# design.net
KiCad netlist of a schematic drawn in Altium Designer
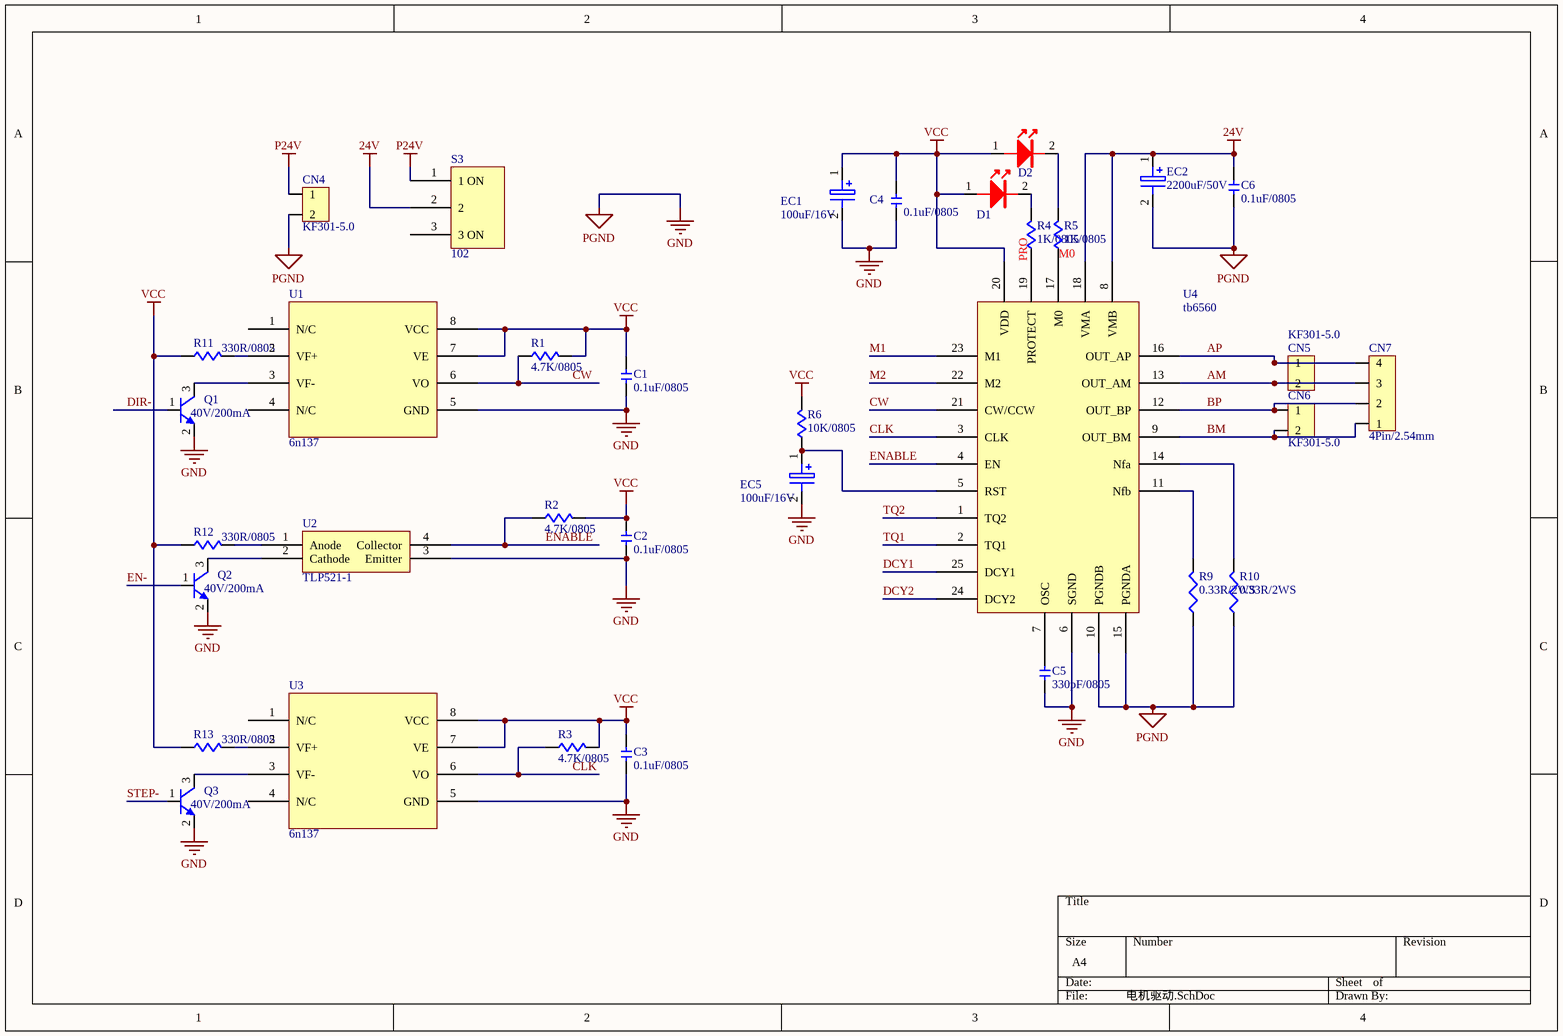
[diagram p0: 电机驱动.SchDoc]

(export (version "E")
  (design (tool "Eeschema 10.0.6"))
  (components
    (comp (ref "C1")
      (value "0.1uF/0805")
      (footprint "WSC0805")
      (description "R21050165/工业C/消费C/贴片电容/0.1uF/±10%/50V/X7R/0805")
      (libsource (lib "Capacitor_21") (part "R21050165"))
    )
    (comp (ref "C2")
      (value "0.1uF/0805")
      (footprint "WSC0805")
      (description "R21050165/工业C/消费C/贴片电容/0.1uF/±10%/50V/X7R/0805")
      (libsource (lib "Capacitor_21") (part "R21050165"))
    )
    (comp (ref "C3")
      (value "0.1uF/0805")
      (footprint "WSC0805")
      (description "R21050165/工业C/消费C/贴片电容/0.1uF/±10%/50V/X7R/0805")
      (libsource (lib "Capacitor_21") (part "R21050165"))
    )
    (comp (ref "C4")
      (value "0.1uF/0805")
      (footprint "WSC0805")
      (description "R21050165/工业C/消费C/贴片电容/0.1uF/±10%/50V/X7R/0805")
      (libsource (lib "Capacitor_21") (part "R21050165"))
    )
    (comp (ref "C5")
      (value "330pF/0805")
      (footprint "WSC0805")
      (description "R21180028/消费C/台系贴片电容/330pF/±10%/50V/X7R/0805")
      (libsource (lib "Capacitor_21") (part "R21180028"))
    )
    (comp (ref "C6")
      (value "0.1uF/0805")
      (footprint "WSC0805")
      (description "R21050005/工业B/消费B/贴片电容/0.1uF±10%/50V/X7R/0805")
      (libsource (lib "Capacitor_21") (part "R21050005"))
    )
    (comp (ref "CN4")
      (value "KF301-5.0")
      (footprint "KF301-5.0")
      (libsource (lib "Integrated_Library1") (part "KF301-5.0"))
    )
    (comp (ref "CN5")
      (value "KF301-5.0")
      (footprint "KF301-5.0")
      (libsource (lib "Integrated_Library1") (part "KF301-5.0"))
    )
    (comp (ref "CN6")
      (value "KF301-5.0")
      (footprint "KF301-5.0")
      (libsource (lib "Integrated_Library1") (part "KF301-5.0"))
    )
    (comp (ref "CN7")
      (value "4Pin/2.54mm")
      (footprint "THT-CON4-2.54-2.54A/S-H8.5")
      (description "R30041122/消费B/普通插座/单排排母/4PIN/3A/单排/直脚/鱼叉母座/2.54mm/-40~105℃/H=8.5mm")
      (libsource (lib "Connector_30") (part "R30041122"))
    )
    (comp (ref "D1")
      (value "LED0805")
      (footprint "SD0805")
      (description "R26010108/工业A/消费A/发光二极管/红色/61mcd@20mA/0805SMD/LED0805")
      (libsource (lib "Semiconductor_26") (part "R26010108"))
    )
    (comp (ref "D2")
      (value "LED0805")
      (footprint "SD0805")
      (description "R26010108/工业A/消费A/发光二极管/红色/61mcd@20mA/0805SMD/LED0805")
      (libsource (lib "Semiconductor_26") (part "R26010108"))
    )
    (comp (ref "EC1")
      (value "100uF/16V")
      (footprint "CAPC2-5-5*11A/D")
      (description "R21010764/消费C/铝电解电容/105℃/100uF/16V/φ5*11")
      (libsource (lib "Capacitor_21") (part "R21010764"))
    )
    (comp (ref "EC2")
      (value "2200uF/50V")
      (footprint "CAPC2-7.5-18*35.5A/S")
      (description "R21110099/工业B/铝电解电容/105℃/2200uF/50V/低阻/φ18*35.5/7000h")
      (libsource (lib "Capacitor_21") (part "R21110099"))
    )
    (comp (ref "EC5")
      (value "100uF/16V")
      (footprint "CAPC2-5-5*11A/D")
      (description "R21010764/消费C/铝电解电容/105℃/100uF/16V/φ5*11")
      (libsource (lib "Capacitor_21") (part "R21010764"))
    )
    (comp (ref "Q1")
      (value "40V/200mA")
      (footprint "WSOT-23")
      (description "R26080001/工业A/消费A/小信号三极管/NPN/40V/200mA/SOT-23")
      (libsource (lib "Semiconductor_26") (part "R26080001"))
    )
    (comp (ref "Q2")
      (value "40V/200mA")
      (footprint "WSOT-23")
      (description "R26080001/工业A/消费A/小信号三极管/NPN/40V/200mA/SOT-23")
      (libsource (lib "Semiconductor_26") (part "R26080001"))
    )
    (comp (ref "Q3")
      (value "40V/200mA")
      (footprint "WSOT-23")
      (description "R26080001/工业A/消费A/小信号三极管/NPN/40V/200mA/SOT-23")
      (libsource (lib "Semiconductor_26") (part "R26080001"))
    )
    (comp (ref "R1")
      (value "4.7K/0805")
      (footprint "WSR0805")
      (description "R20180039/工业A/消费A/贴片电阻/1/8W/4.7KΩ±5%/0805")
      (libsource (lib "Resistor_20") (part "R20180039"))
    )
    (comp (ref "R2")
      (value "4.7K/0805")
      (footprint "WSR0805")
      (description "R20180039/工业A/消费A/贴片电阻/1/8W/4.7KΩ±5%/0805")
      (libsource (lib "Resistor_20") (part "R20180039"))
    )
    (comp (ref "R3")
      (value "4.7K/0805")
      (footprint "WSR0805")
      (description "R20180039/工业A/消费A/贴片电阻/1/8W/4.7KΩ±5%/0805")
      (libsource (lib "Resistor_20") (part "R20180039"))
    )
    (comp (ref "R4")
      (value "1K/0805")
      (footprint "WSR0805")
      (description "R20180023/工业A/消费A/贴片电阻/1/8W/1KΩ±5%/0805")
      (libsource (lib "Resistor_20") (part "R20180023"))
    )
    (comp (ref "R5")
      (value "1K/0805")
      (footprint "WSR0805")
      (description "R20180023/工业A/消费A/贴片电阻/1/8W/1KΩ±5%/0805")
      (libsource (lib "Resistor_20") (part "R20180023"))
    )
    (comp (ref "R6")
      (value "10K/0805")
      (footprint "WSR0805")
      (description "R20180048/工业A/消费A/贴片电阻/1/8W/10KΩ±5%/0805")
      (libsource (lib "Resistor_20") (part "R20180048"))
    )
    (comp (ref "R9")
      (value "0.33R/2WS")
      (footprint "R2-7.5-4.5A/S")
      (description "R20040079/工业B/消费B/无感线绕电阻/2WS/0.33Ω±5%/小型4.5*11")
      (libsource (lib "Resistor_20") (part "R20040079"))
    )
    (comp (ref "R10")
      (value "0.33R/2WS")
      (footprint "R2-7.5-4.5A/S")
      (description "R20040079/工业B/消费B/无感线绕电阻/2WS/0.33Ω±5%/小型4.5*11")
      (libsource (lib "Resistor_20") (part "R20040079"))
    )
    (comp (ref "R11")
      (value "330R/0805")
      (footprint "WSR0805")
      (description "R20180090/工业A/消费A/贴片电阻/1/8W/330Ω±5%/0805")
      (libsource (lib "Resistor_20") (part "R20180090"))
    )
    (comp (ref "R12")
      (value "330R/0805")
      (footprint "WSR0805")
      (description "R20180090/工业A/消费A/贴片电阻/1/8W/330Ω±5%/0805")
      (libsource (lib "Resistor_20") (part "R20180090"))
    )
    (comp (ref "R13")
      (value "330R/0805")
      (footprint "WSR0805")
      (description "R20180090/工业A/消费A/贴片电阻/1/8W/330Ω±5%/0805")
      (libsource (lib "Resistor_20") (part "R20180090"))
    )
    (comp (ref "S3")
      (value "102")
      (footprint "开关")
      (libsource (lib "Integrated_Library1") (part "switch mts102"))
    )
    (comp (ref "U1")
      (value "6n137")
      (footprint "6N137")
      (description "6n137高速度光耦")
      (libsource (lib "Integrated_Library1") (part "6n137"))
    )
    (comp (ref "U2")
      (value "TLP521-1")
      (footprint "tlp521 - duplicate")
      (description "TLP521-1/光耦")
      (libsource (lib "Integrated_Library1") (part "TLP521"))
    )
    (comp (ref "U3")
      (value "6n137")
      (footprint "6N137")
      (description "6n137高速度光耦")
      (libsource (lib "Integrated_Library1") (part "6n137"))
    )
    (comp (ref "U4")
      (value "tb6560")
      (footprint "TB6560")
      (description "tb6560、步进电机驱动")
      (libsource (lib "Integrated_Library1") (part "tb6560"))
    )
  )
  (nets
    (net (code "1") (name "/AM") (class "Default")
      (node (ref "CN5") (pin "2") (pinfunction "2_2") (pintype "passive"))
      (node (ref "CN7") (pin "3") (pinfunction "3_3") (pintype "passive"))
      (node (ref "U4") (pin "13") (pinfunction "OUT_AM_13") (pintype "passive"))
    )
    (net (code "2") (name "/AP") (class "Default")
      (node (ref "CN5") (pin "1") (pinfunction "1_1") (pintype "passive"))
      (node (ref "CN7") (pin "4") (pinfunction "4_4") (pintype "passive"))
      (node (ref "U4") (pin "16") (pinfunction "OUT_AP_16") (pintype "passive"))
    )
    (net (code "3") (name "/BM") (class "Default")
      (node (ref "CN6") (pin "2") (pinfunction "2_2") (pintype "passive"))
      (node (ref "CN7") (pin "1") (pinfunction "1_1") (pintype "passive"))
      (node (ref "U4") (pin "9") (pinfunction "OUT_BM_9") (pintype "passive"))
    )
    (net (code "4") (name "/BP") (class "Default")
      (node (ref "CN6") (pin "1") (pinfunction "1_1") (pintype "passive"))
      (node (ref "CN7") (pin "2") (pinfunction "2_2") (pintype "passive"))
      (node (ref "U4") (pin "12") (pinfunction "OUT_BP_12") (pintype "passive"))
    )
    (net (code "5") (name "/CLK") (class "Default")
      (node (ref "R3") (pin "1") (pinfunction "1_1") (pintype "passive"))
      (node (ref "U3") (pin "6") (pinfunction "VO_6") (pintype "passive"))
      (node (ref "U4") (pin "3") (pinfunction "CLK_3") (pintype "passive"))
    )
    (net (code "6") (name "/CW") (class "Default")
      (node (ref "R1") (pin "1") (pinfunction "1_1") (pintype "passive"))
      (node (ref "U1") (pin "6") (pinfunction "VO_6") (pintype "passive"))
      (node (ref "U4") (pin "21") (pinfunction "CW/CCW_21") (pintype "passive"))
    )
    (net (code "7") (name "/DCY1") (class "Default")
      (node (ref "U4") (pin "25") (pinfunction "DCY1_25") (pintype "passive"))
    )
    (net (code "8") (name "/DCY2") (class "Default")
      (node (ref "U4") (pin "24") (pinfunction "DCY2_24") (pintype "passive"))
    )
    (net (code "9") (name "/DIR-") (class "Default")
      (node (ref "Q1") (pin "1") (pinfunction "B_1") (pintype "passive"))
    )
    (net (code "10") (name "/EN-") (class "Default")
      (node (ref "Q2") (pin "1") (pinfunction "B_1") (pintype "passive"))
    )
    (net (code "11") (name "/ENABLE") (class "Default")
      (node (ref "R2") (pin "1") (pinfunction "1_1") (pintype "passive"))
      (node (ref "U2") (pin "4") (pinfunction "Collector_4") (pintype "passive"))
      (node (ref "U4") (pin "4") (pinfunction "EN_4") (pintype "passive"))
    )
    (net (code "12") (name "/M0") (class "Default")
      (node (ref "R5") (pin "1") (pinfunction "1_1") (pintype "passive"))
      (node (ref "U4") (pin "17") (pinfunction "M0_17") (pintype "passive"))
    )
    (net (code "13") (name "/M1") (class "Default")
      (node (ref "U4") (pin "23") (pinfunction "M1_23") (pintype "passive"))
    )
    (net (code "14") (name "/M2") (class "Default")
      (node (ref "U4") (pin "22") (pinfunction "M2_22") (pintype "passive"))
    )
    (net (code "15") (name "/PRO") (class "Default")
      (node (ref "R4") (pin "1") (pinfunction "1_1") (pintype "passive"))
      (node (ref "U4") (pin "19") (pinfunction "PROTECT_19") (pintype "passive"))
    )
    (net (code "16") (name "/STEP-") (class "Default")
      (node (ref "Q3") (pin "1") (pinfunction "B_1") (pintype "passive"))
    )
    (net (code "17") (name "/TQ1") (class "Default")
      (node (ref "U4") (pin "2") (pinfunction "TQ1_2") (pintype "passive"))
    )
    (net (code "18") (name "/TQ2") (class "Default")
      (node (ref "U4") (pin "1") (pinfunction "TQ2_1") (pintype "passive"))
    )
    (net (code "19") (name "24V") (class "Default")
      (node (ref "C6") (pin "2") (pinfunction "2_2") (pintype "passive"))
      (node (ref "EC2") (pin "1") (pinfunction "1_1") (pintype "passive"))
      (node (ref "S3") (pin "2") (pinfunction "2_2") (pintype "passive"))
      (node (ref "U4") (pin "18") (pinfunction "VMA_18") (pintype "passive"))
      (node (ref "U4") (pin "8") (pinfunction "VMB_8") (pintype "passive"))
    )
    (net (code "20") (name "GND") (class "Default")
      (node (ref "C1") (pin "1") (pinfunction "1_1") (pintype "passive"))
      (node (ref "C2") (pin "1") (pinfunction "1_1") (pintype "passive"))
      (node (ref "C3") (pin "1") (pinfunction "1_1") (pintype "passive"))
      (node (ref "C4") (pin "1") (pinfunction "1_1") (pintype "passive"))
      (node (ref "C5") (pin "1") (pinfunction "1_1") (pintype "passive"))
      (node (ref "C6") (pin "1") (pinfunction "1_1") (pintype "passive"))
      (node (ref "CN4") (pin "2") (pinfunction "2_2") (pintype "passive"))
      (node (ref "EC1") (pin "2") (pinfunction "2_2") (pintype "passive"))
      (node (ref "EC2") (pin "2") (pinfunction "2_2") (pintype "passive"))
      (node (ref "EC5") (pin "2") (pinfunction "2_2") (pintype "passive"))
      (node (ref "Q1") (pin "2") (pinfunction "E_2") (pintype "passive"))
      (node (ref "Q2") (pin "2") (pinfunction "E_2") (pintype "passive"))
      (node (ref "Q3") (pin "2") (pinfunction "E_2") (pintype "passive"))
      (node (ref "R10") (pin "1") (pinfunction "1_1") (pintype "passive"))
      (node (ref "R9") (pin "1") (pinfunction "1_1") (pintype "passive"))
      (node (ref "U1") (pin "5") (pinfunction "GND_5") (pintype "passive"))
      (node (ref "U2") (pin "3") (pinfunction "Emitter_3") (pintype "passive"))
      (node (ref "U3") (pin "5") (pinfunction "GND_5") (pintype "passive"))
      (node (ref "U4") (pin "10") (pinfunction "PGNDB_10") (pintype "passive"))
      (node (ref "U4") (pin "15") (pinfunction "PGNDA_15") (pintype "passive"))
      (node (ref "U4") (pin "6") (pinfunction "SGND_6") (pintype "passive"))
    )
    (net (code "21") (name "Net-(D1-K)") (class "Default")
      (node (ref "D1") (pin "2") (pinfunction "K_2") (pintype "passive"))
      (node (ref "R4") (pin "2") (pinfunction "2_2") (pintype "passive"))
    )
    (net (code "22") (name "Net-(D2-K)") (class "Default")
      (node (ref "D2") (pin "2") (pinfunction "K_2") (pintype "passive"))
      (node (ref "R5") (pin "2") (pinfunction "2_2") (pintype "passive"))
    )
    (net (code "23") (name "Net-(Q1-C)") (class "Default")
      (node (ref "Q1") (pin "3") (pinfunction "C_3") (pintype "passive"))
      (node (ref "U1") (pin "3") (pinfunction "VF-_3") (pintype "passive"))
    )
    (net (code "24") (name "Net-(Q2-C)") (class "Default")
      (node (ref "Q2") (pin "3") (pinfunction "C_3") (pintype "passive"))
      (node (ref "U2") (pin "2") (pinfunction "Cathode_2") (pintype "passive"))
    )
    (net (code "25") (name "Net-(Q3-C)") (class "Default")
      (node (ref "Q3") (pin "3") (pinfunction "C_3") (pintype "passive"))
      (node (ref "U3") (pin "3") (pinfunction "VF-_3") (pintype "passive"))
    )
    (net (code "26") (name "Net-(U1-VF+)") (class "Default")
      (node (ref "R11") (pin "2") (pinfunction "2_2") (pintype "passive"))
      (node (ref "U1") (pin "2") (pinfunction "VF+_2") (pintype "passive"))
    )
    (net (code "27") (name "Net-(U2-Anode)") (class "Default")
      (node (ref "R12") (pin "2") (pinfunction "2_2") (pintype "passive"))
      (node (ref "U2") (pin "1") (pinfunction "Anode_1") (pintype "passive"))
    )
    (net (code "28") (name "Net-(U3-VF+)") (class "Default")
      (node (ref "R13") (pin "2") (pinfunction "2_2") (pintype "passive"))
      (node (ref "U3") (pin "2") (pinfunction "VF+_2") (pintype "passive"))
    )
    (net (code "29") (name "Net-(U4-Nfa)") (class "Default")
      (node (ref "R10") (pin "2") (pinfunction "2_2") (pintype "passive"))
      (node (ref "U4") (pin "14") (pinfunction "Nfa_14") (pintype "passive"))
    )
    (net (code "30") (name "Net-(U4-Nfb)") (class "Default")
      (node (ref "R9") (pin "2") (pinfunction "2_2") (pintype "passive"))
      (node (ref "U4") (pin "11") (pinfunction "Nfb_11") (pintype "passive"))
    )
    (net (code "31") (name "Net-(U4-OSC)") (class "Default")
      (node (ref "C5") (pin "2") (pinfunction "2_2") (pintype "passive"))
      (node (ref "U4") (pin "7") (pinfunction "OSC_7") (pintype "passive"))
    )
    (net (code "32") (name "Net-(U4-RST)") (class "Default")
      (node (ref "EC5") (pin "1") (pinfunction "1_1") (pintype "passive"))
      (node (ref "R6") (pin "1") (pinfunction "1_1") (pintype "passive"))
      (node (ref "U4") (pin "5") (pinfunction "RST_5") (pintype "passive"))
    )
    (net (code "33") (name "P24V") (class "Default")
      (node (ref "CN4") (pin "1") (pinfunction "1_1") (pintype "passive"))
      (node (ref "S3") (pin "1") (pinfunction "1_ON_1") (pintype "passive"))
    )
    (net (code "34") (name "VCC") (class "Default")
      (node (ref "C1") (pin "2") (pinfunction "2_2") (pintype "passive"))
      (node (ref "C2") (pin "2") (pinfunction "2_2") (pintype "passive"))
      (node (ref "C3") (pin "2") (pinfunction "2_2") (pintype "passive"))
      (node (ref "C4") (pin "2") (pinfunction "2_2") (pintype "passive"))
      (node (ref "D1") (pin "1") (pinfunction "A_1") (pintype "passive"))
      (node (ref "D2") (pin "1") (pinfunction "A_1") (pintype "passive"))
      (node (ref "EC1") (pin "1") (pinfunction "1_1") (pintype "passive"))
      (node (ref "R1") (pin "2") (pinfunction "2_2") (pintype "passive"))
      (node (ref "R11") (pin "1") (pinfunction "1_1") (pintype "passive"))
      (node (ref "R12") (pin "1") (pinfunction "1_1") (pintype "passive"))
      (node (ref "R13") (pin "1") (pinfunction "1_1") (pintype "passive"))
      (node (ref "R2") (pin "2") (pinfunction "2_2") (pintype "passive"))
      (node (ref "R3") (pin "2") (pinfunction "2_2") (pintype "passive"))
      (node (ref "R6") (pin "2") (pinfunction "2_2") (pintype "passive"))
      (node (ref "U1") (pin "7") (pinfunction "VE_7") (pintype "passive"))
      (node (ref "U1") (pin "8") (pinfunction "VCC_8") (pintype "passive"))
      (node (ref "U3") (pin "7") (pinfunction "VE_7") (pintype "passive"))
      (node (ref "U3") (pin "8") (pinfunction "VCC_8") (pintype "passive"))
      (node (ref "U4") (pin "20") (pinfunction "VDD_20") (pintype "passive"))
    )
    (net (code "35") (name "unconnected-(S3-3_ON-Pad3)") (class "Default")
      (node (ref "S3") (pin "3") (pinfunction "3_ON_3") (pintype "passive"))
    )
    (net (code "36") (name "unconnected-(U1-N{slash}C-Pad1)") (class "Default")
      (node (ref "U1") (pin "1") (pinfunction "N/C_1") (pintype "passive"))
    )
    (net (code "37") (name "unconnected-(U1-N{slash}C-Pad4)") (class "Default")
      (node (ref "U1") (pin "4") (pinfunction "N/C_4") (pintype "passive"))
    )
    (net (code "38") (name "unconnected-(U3-N{slash}C-Pad1)") (class "Default")
      (node (ref "U3") (pin "1") (pinfunction "N/C_1") (pintype "passive"))
    )
    (net (code "39") (name "unconnected-(U3-N{slash}C-Pad4)") (class "Default")
      (node (ref "U3") (pin "4") (pinfunction "N/C_4") (pintype "passive"))
    )
  )
)
